# AMP.net
KiCad netlist of a schematic drawn in Altium Designer
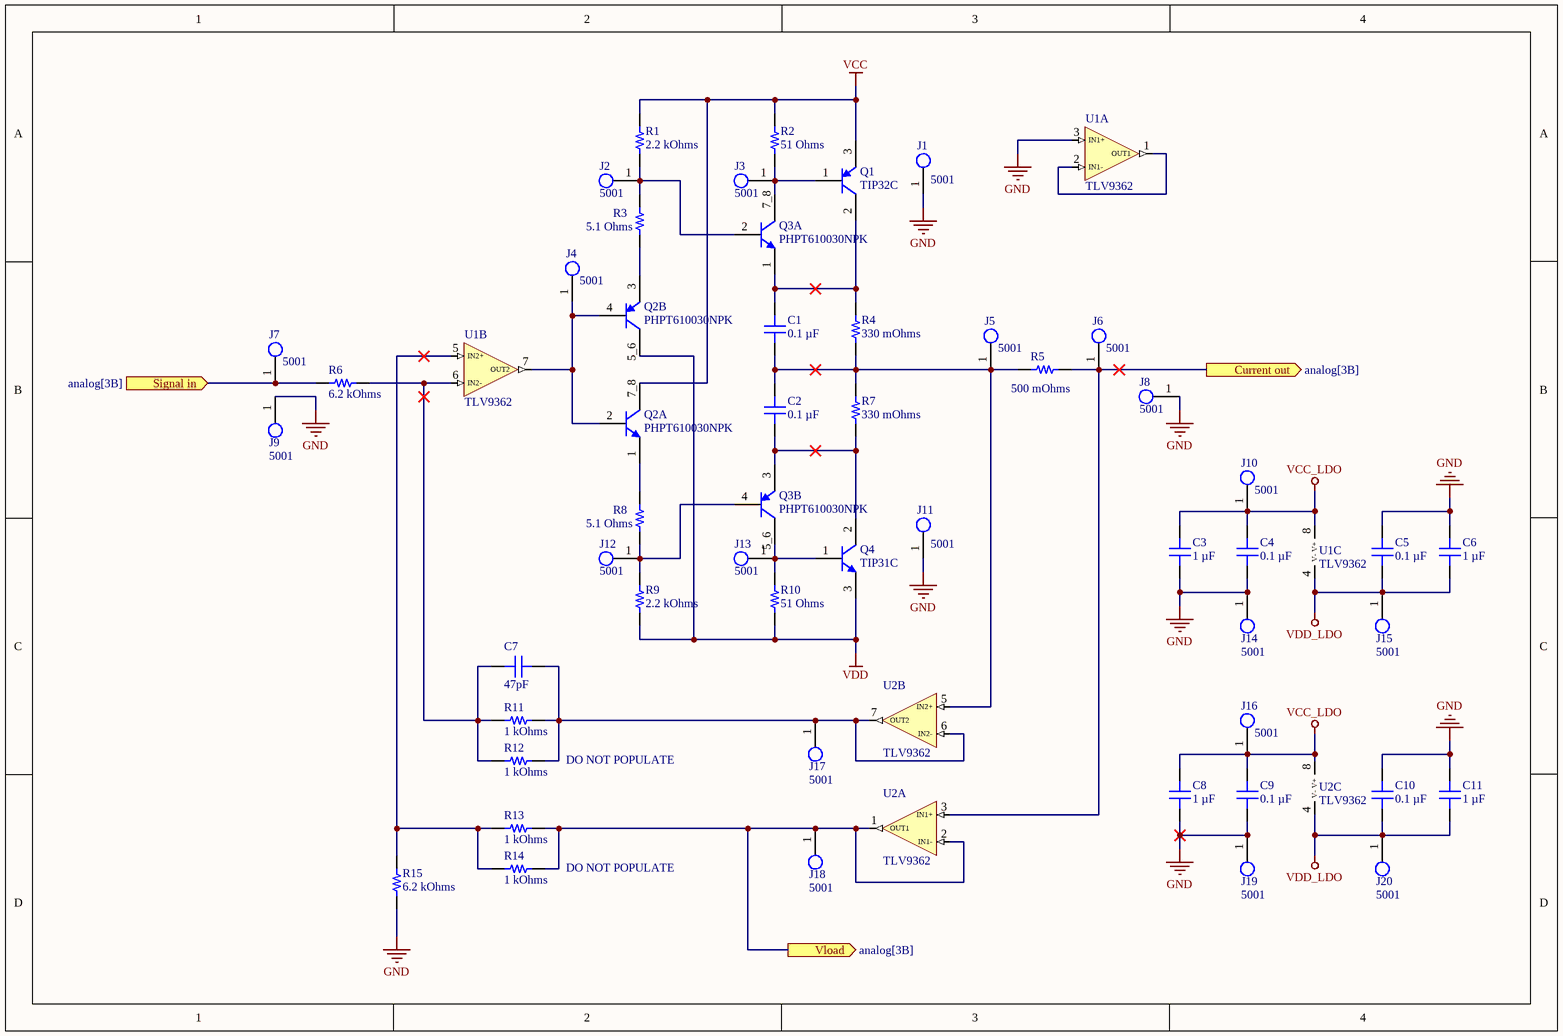
[diagram p0: AMP.SchDoc]

(export (version "E")
  (design (tool "Eeschema 10.0.6"))
  (components
    (comp (ref "C1")
      (value "0.1 µF")
      (footprint "CAP 1206_3216 - 0.8MM")
      (description "CAP CER 0.1UF 50V X7R 1206")
      (fields
        (field (name "PART NUMBER") "885012208087")
        (field (name "CAPACITANCE") "0.1 µF")
        (field (name "MANUFACTURER") "Würth Elektronik")
      )
      (libsource (lib "Celestial Altium Library - altium_library") (part "Capacitor"))
    )
    (comp (ref "C2")
      (value "0.1 µF")
      (footprint "CAP 1206_3216 - 0.8MM")
      (description "CAP CER 0.1UF 50V X7R 1206")
      (fields
        (field (name "PART NUMBER") "885012208087")
        (field (name "CAPACITANCE") "0.1 µF")
        (field (name "MANUFACTURER") "Würth Elektronik")
      )
      (libsource (lib "Celestial Altium Library - altium_library") (part "Capacitor"))
    )
    (comp (ref "C3")
      (value "1 µF")
      (footprint "CAP 1206_3216 - 0.8MM")
      (description "CAP CER 1UF 50V X7R 1206")
      (fields
        (field (name "PART NUMBER") "885012208093")
        (field (name "CAPACITANCE") "1 µF")
        (field (name "MANUFACTURER") "Würth Elektronik")
      )
      (libsource (lib "Celestial Altium Library - altium_library") (part "Capacitor"))
    )
    (comp (ref "C4")
      (value "0.1 µF")
      (footprint "CAP 1206_3216 - 0.8MM")
      (description "CAP CER 0.1UF 50V X7R 1206")
      (fields
        (field (name "PART NUMBER") "885012208087")
        (field (name "CAPACITANCE") "0.1 µF")
        (field (name "MANUFACTURER") "Würth Elektronik")
      )
      (libsource (lib "Celestial Altium Library - altium_library") (part "Capacitor"))
    )
    (comp (ref "C5")
      (value "0.1 µF")
      (footprint "CAP 1206_3216 - 0.8MM")
      (description "CAP CER 0.1UF 50V X7R 1206")
      (fields
        (field (name "PART NUMBER") "885012208087")
        (field (name "CAPACITANCE") "0.1 µF")
        (field (name "MANUFACTURER") "Würth Elektronik")
      )
      (libsource (lib "Celestial Altium Library - altium_library") (part "Capacitor"))
    )
    (comp (ref "C6")
      (value "1 µF")
      (footprint "CAP 1206_3216 - 0.8MM")
      (description "CAP CER 1UF 50V X7R 1206")
      (fields
        (field (name "PART NUMBER") "885012208093")
        (field (name "CAPACITANCE") "1 µF")
        (field (name "MANUFACTURER") "Würth Elektronik")
      )
      (libsource (lib "Celestial Altium Library - altium_library") (part "Capacitor"))
    )
    (comp (ref "C7")
      (value "47pF")
      (footprint "CAP 1206_3216 - 1.8MM")
      (description "CAP CER 47PF 1KV C0G/NP0 1206")
      (fields
        (field (name "PART NUMBER") "1206AA470KAT1A")
        (field (name "CAPACITANCE") "47pF")
        (field (name "MANUFACTURER") "AVX Corporation")
      )
      (libsource (lib "Celestial Altium Library - altium_library") (part "Capacitor"))
    )
    (comp (ref "C8")
      (value "1 µF")
      (footprint "CAP 1206_3216 - 0.8MM")
      (description "CAP CER 1UF 50V X7R 1206")
      (fields
        (field (name "PART NUMBER") "885012208093")
        (field (name "CAPACITANCE") "1 µF")
        (field (name "MANUFACTURER") "Würth Elektronik")
      )
      (libsource (lib "Celestial Altium Library - altium_library") (part "Capacitor"))
    )
    (comp (ref "C9")
      (value "0.1 µF")
      (footprint "CAP 1206_3216 - 0.8MM")
      (description "CAP CER 0.1UF 50V X7R 1206")
      (fields
        (field (name "PART NUMBER") "885012208087")
        (field (name "CAPACITANCE") "0.1 µF")
        (field (name "MANUFACTURER") "Würth Elektronik")
      )
      (libsource (lib "Celestial Altium Library - altium_library") (part "Capacitor"))
    )
    (comp (ref "C10")
      (value "0.1 µF")
      (footprint "CAP 1206_3216 - 0.8MM")
      (description "CAP CER 0.1UF 50V X7R 1206")
      (fields
        (field (name "PART NUMBER") "885012208087")
        (field (name "CAPACITANCE") "0.1 µF")
        (field (name "MANUFACTURER") "Würth Elektronik")
      )
      (libsource (lib "Celestial Altium Library - altium_library") (part "Capacitor"))
    )
    (comp (ref "C11")
      (value "1 µF")
      (footprint "CAP 1206_3216 - 0.8MM")
      (description "CAP CER 1UF 50V X7R 1206")
      (fields
        (field (name "PART NUMBER") "885012208093")
        (field (name "CAPACITANCE") "1 µF")
        (field (name "MANUFACTURER") "Würth Elektronik")
      )
      (libsource (lib "Celestial Altium Library - altium_library") (part "Capacitor"))
    )
    (comp (ref "J1")
      (value "5001")
      (footprint "FP-5001-MFG")
      (description "PC TEST POINT MINIATURE BLACK")
      (libsource (lib "za_koncar") (part "CMP-2000-05181-2"))
    )
    (comp (ref "J2")
      (value "5001")
      (footprint "FP-5001-MFG")
      (description "PC TEST POINT MINIATURE BLACK")
      (libsource (lib "za_koncar") (part "CMP-2000-05181-2"))
    )
    (comp (ref "J3")
      (value "5001")
      (footprint "FP-5001-MFG")
      (description "PC TEST POINT MINIATURE BLACK")
      (libsource (lib "za_koncar") (part "CMP-2000-05181-2"))
    )
    (comp (ref "J4")
      (value "5001")
      (footprint "FP-5001-MFG")
      (description "PC TEST POINT MINIATURE BLACK")
      (libsource (lib "za_koncar") (part "CMP-2000-05181-2"))
    )
    (comp (ref "J5")
      (value "5001")
      (footprint "FP-5001-MFG")
      (description "PC TEST POINT MINIATURE BLACK")
      (libsource (lib "za_koncar") (part "CMP-2000-05181-2"))
    )
    (comp (ref "J6")
      (value "5001")
      (footprint "FP-5001-MFG")
      (description "PC TEST POINT MINIATURE BLACK")
      (libsource (lib "za_koncar") (part "CMP-2000-05181-2"))
    )
    (comp (ref "J7")
      (value "5001")
      (footprint "FP-5001-MFG")
      (description "PC TEST POINT MINIATURE BLACK")
      (libsource (lib "za_koncar") (part "CMP-2000-05181-2"))
    )
    (comp (ref "J8")
      (value "5001")
      (footprint "FP-5001-MFG")
      (description "PC TEST POINT MINIATURE BLACK")
      (libsource (lib "za_koncar") (part "CMP-2000-05181-2"))
    )
    (comp (ref "J9")
      (value "5001")
      (footprint "FP-5001-MFG")
      (description "PC TEST POINT MINIATURE BLACK")
      (libsource (lib "za_koncar") (part "CMP-2000-05181-2"))
    )
    (comp (ref "J10")
      (value "5001")
      (footprint "FP-5001-MFG")
      (description "PC TEST POINT MINIATURE BLACK")
      (libsource (lib "za_koncar") (part "CMP-2000-05181-2"))
    )
    (comp (ref "J11")
      (value "5001")
      (footprint "FP-5001-MFG")
      (description "PC TEST POINT MINIATURE BLACK")
      (libsource (lib "za_koncar") (part "CMP-2000-05181-2"))
    )
    (comp (ref "J12")
      (value "5001")
      (footprint "FP-5001-MFG")
      (description "PC TEST POINT MINIATURE BLACK")
      (libsource (lib "za_koncar") (part "CMP-2000-05181-2"))
    )
    (comp (ref "J13")
      (value "5001")
      (footprint "FP-5001-MFG")
      (description "PC TEST POINT MINIATURE BLACK")
      (libsource (lib "za_koncar") (part "CMP-2000-05181-2"))
    )
    (comp (ref "J14")
      (value "5001")
      (footprint "FP-5001-MFG")
      (description "PC TEST POINT MINIATURE BLACK")
      (libsource (lib "za_koncar") (part "CMP-2000-05181-2"))
    )
    (comp (ref "J15")
      (value "5001")
      (footprint "FP-5001-MFG")
      (description "PC TEST POINT MINIATURE BLACK")
      (libsource (lib "za_koncar") (part "CMP-2000-05181-2"))
    )
    (comp (ref "J16")
      (value "5001")
      (footprint "FP-5001-MFG")
      (description "PC TEST POINT MINIATURE BLACK")
      (libsource (lib "za_koncar") (part "CMP-2000-05181-2"))
    )
    (comp (ref "J17")
      (value "5001")
      (footprint "FP-5001-MFG")
      (description "PC TEST POINT MINIATURE BLACK")
      (libsource (lib "za_koncar") (part "CMP-2000-05181-2"))
    )
    (comp (ref "J18")
      (value "5001")
      (footprint "FP-5001-MFG")
      (description "PC TEST POINT MINIATURE BLACK")
      (libsource (lib "za_koncar") (part "CMP-2000-05181-2"))
    )
    (comp (ref "J19")
      (value "5001")
      (footprint "FP-5001-MFG")
      (description "PC TEST POINT MINIATURE BLACK")
      (libsource (lib "za_koncar") (part "CMP-2000-05181-2"))
    )
    (comp (ref "J20")
      (value "5001")
      (footprint "FP-5001-MFG")
      (description "PC TEST POINT MINIATURE BLACK")
      (libsource (lib "za_koncar") (part "CMP-2000-05181-2"))
    )
    (comp (ref "Q1")
      (value "TIP32C")
      (footprint "ONSC-TO-220-3-221A-09")
      (description "Complementary Silicon Plastic Power Transistor, 3-Pin TO-220, Tube")
      (fields (field (name "MANUFACTURER") "On Semiconductor"))
      (libsource (lib "ON Semi General Purpose Transistors") (part "TIP32C"))
    )
    (comp (ref "Q2")
      (value "PHPT610030NPK")
      (footprint "TRANS_BUK9K18-40E,115")
      (libsource (lib "za_koncar") (part "PHPT610030NPK"))
    )
    (comp (ref "Q3")
      (value "PHPT610030NPK")
      (footprint "TRANS_BUK9K18-40E,115")
      (libsource (lib "za_koncar") (part "PHPT610030NPK"))
    )
    (comp (ref "Q4")
      (value "TIP31C")
      (footprint "ONSC-TO-220-3-221A-09")
      (description "Complementary Silicon Plastic Power Transistor, 3-Pin TO-220, Tube")
      (fields (field (name "MANUFACTURER") "On Semiconductor"))
      (libsource (lib "ON Semi General Purpose Transistors") (part "TIP31C"))
    )
    (comp (ref "R1")
      (value "2.2 kOhms")
      (footprint "RES 1206_3216")
      (description "RES SMD 2.2K OHM 5% 1/4W 1206")
      (fields
        (field (name "PART NUMBER") "ERJ-8GEYJ222V")
        (field (name "MANUFACTURER") "Panasonic Electronic Components")
      )
      (libsource (lib "Celestial Altium Library - altium_library") (part "Resistor"))
    )
    (comp (ref "R2")
      (value "51 Ohms")
      (footprint "RES 1206_3216")
      (description "RES SMD 51 OHM 5% 1/4W 1206")
      (fields
        (field (name "PART NUMBER") "ERJ-8GEYJ510V")
        (field (name "MANUFACTURER") "Panasonic Electronic Components")
      )
      (libsource (lib "Celestial Altium Library - altium_library") (part "Resistor"))
    )
    (comp (ref "R3")
      (value "5.1 Ohms")
      (footprint "RES 1206_3216")
      (description "RES SMD 5.1 OHM 5% 1/4W 1206")
      (fields
        (field (name "PART NUMBER") "ERJ-8GEYJ5R1V")
        (field (name "MANUFACTURER") "Panasonic Electronic Components")
      )
      (libsource (lib "Celestial Altium Library - altium_library") (part "Resistor"))
    )
    (comp (ref "R4")
      (value "330 mOhms")
      (footprint "STACKPOLE CSR2512")
      (description "RES 0.33 OHM 1% 2W 2512")
      (fields
        (field (name "PART NUMBER") "CSRN2512FKR330")
        (field (name "MANUFACTURER") "Stackpole Electronics Inc")
      )
      (libsource (lib "Celestial Altium Library - altium_library") (part "Resistor"))
    )
    (comp (ref "R5")
      (value "500 mOhms")
      (footprint "STACKPOLE CSR2512")
      (description "RES 0.5 OHM 1% 2W 2512")
      (fields
        (field (name "PART NUMBER") "CSRN2512FKR500")
        (field (name "MANUFACTURER") "Stackpole Electronics Inc")
      )
      (libsource (lib "Celestial Altium Library - altium_library") (part "Resistor"))
    )
    (comp (ref "R6")
      (value "6.2 kOhms")
      (footprint "RES 1206_3216")
      (description "RES SMD 6.2K OHM 0.1% 1/4W 1206")
      (fields
        (field (name "PART NUMBER") "ERA-8AEB622V")
        (field (name "MANUFACTURER") "Panasonic Electronic Components")
      )
      (libsource (lib "Celestial Altium Library - altium_library") (part "Resistor"))
    )
    (comp (ref "R7")
      (value "330 mOhms")
      (footprint "STACKPOLE CSR2512")
      (description "RES 0.33 OHM 1% 2W 2512")
      (fields
        (field (name "PART NUMBER") "CSRN2512FKR330")
        (field (name "MANUFACTURER") "Stackpole Electronics Inc")
      )
      (libsource (lib "Celestial Altium Library - altium_library") (part "Resistor"))
    )
    (comp (ref "R8")
      (value "5.1 Ohms")
      (footprint "RES 1206_3216")
      (description "RES SMD 5.1 OHM 5% 1/4W 1206")
      (fields
        (field (name "PART NUMBER") "ERJ-8GEYJ5R1V")
        (field (name "MANUFACTURER") "Panasonic Electronic Components")
      )
      (libsource (lib "Celestial Altium Library - altium_library") (part "Resistor"))
    )
    (comp (ref "R9")
      (value "2.2 kOhms")
      (footprint "RES 1206_3216")
      (description "RES SMD 2.2K OHM 5% 1/4W 1206")
      (fields
        (field (name "PART NUMBER") "ERJ-8GEYJ222V")
        (field (name "MANUFACTURER") "Panasonic Electronic Components")
      )
      (libsource (lib "Celestial Altium Library - altium_library") (part "Resistor"))
    )
    (comp (ref "R10")
      (value "51 Ohms")
      (footprint "RES 1206_3216")
      (description "RES SMD 51 OHM 5% 1/4W 1206")
      (fields
        (field (name "PART NUMBER") "ERJ-8GEYJ510V")
        (field (name "MANUFACTURER") "Panasonic Electronic Components")
      )
      (libsource (lib "Celestial Altium Library - altium_library") (part "Resistor"))
    )
    (comp (ref "R11")
      (value "1 kOhms")
      (footprint "RES 1206_3216")
      (description "RES SMD 1K OHM 0.1% 1/4W 1206")
      (fields
        (field (name "PART NUMBER") "ERA-8AEB102V")
        (field (name "MANUFACTURER") "Panasonic Electronic Components")
      )
      (libsource (lib "Celestial Altium Library - altium_library") (part "Resistor"))
    )
    (comp (ref "R12")
      (value "1 kOhms")
      (footprint "RES 1206_3216")
      (description "RES SMD 1K OHM 0.1% 1/4W 1206")
      (fields
        (field (name "PART NUMBER") "ERA-8AEB102V")
        (field (name "MANUFACTURER") "Panasonic Electronic Components")
      )
      (libsource (lib "Celestial Altium Library - altium_library") (part "Resistor"))
    )
    (comp (ref "R13")
      (value "1 kOhms")
      (footprint "RES 1206_3216")
      (description "RES SMD 1K OHM 0.1% 1/4W 1206")
      (fields
        (field (name "PART NUMBER") "ERA-8AEB102V")
        (field (name "MANUFACTURER") "Panasonic Electronic Components")
      )
      (libsource (lib "Celestial Altium Library - altium_library") (part "Resistor"))
    )
    (comp (ref "R14")
      (value "1 kOhms")
      (footprint "RES 1206_3216")
      (description "RES SMD 1K OHM 0.1% 1/4W 1206")
      (fields
        (field (name "PART NUMBER") "ERA-8AEB102V")
        (field (name "MANUFACTURER") "Panasonic Electronic Components")
      )
      (libsource (lib "Celestial Altium Library - altium_library") (part "Resistor"))
    )
    (comp (ref "R15")
      (value "6.2 kOhms")
      (footprint "RES 1206_3216")
      (description "RES SMD 6.2K OHM 0.1% 1/4W 1206")
      (fields
        (field (name "PART NUMBER") "ERA-8AEB622V")
        (field (name "MANUFACTURER") "Panasonic Electronic Components")
      )
      (libsource (lib "Celestial Altium Library - altium_library") (part "Resistor"))
    )
    (comp (ref "U1")
      (value "TLV9362")
      (footprint "za_koncar:SOIC8-127P600X175-8N")
      (description "TLV936x 10-MHz, 40-V, RRO, Operational Amplifie")
      (libsource (lib "za_koncar") (part "TLV9362"))
    )
    (comp (ref "U2")
      (value "TLV9362")
      (footprint "za_koncar:SOIC8-127P600X175-8N")
      (description "TLV936x 10-MHz, 40-V, RRO, Operational Amplifie")
      (libsource (lib "za_koncar") (part "TLV9362"))
    )
  )
  (nets
    (net (code "1") (name "/Current out") (class "Default")
      (node (ref "J6") (pin "1") (pinfunction "1_1") (pintype "passive"))
      (node (ref "R5") (pin "1") (pinfunction "1_1") (pintype "passive"))
      (node (ref "U2") (pin "3") (pinfunction "IN1+_3") (pintype "input"))
    )
    (net (code "2") (name "/Signal in") (class "Default")
      (node (ref "J7") (pin "1") (pinfunction "1_1") (pintype "passive"))
      (node (ref "R6") (pin "2") (pinfunction "2_2") (pintype "passive"))
    )
    (net (code "3") (name "/Vload") (class "Default")
      (node (ref "J18") (pin "1") (pinfunction "1_1") (pintype "passive"))
      (node (ref "R13") (pin "2") (pinfunction "2_2") (pintype "passive"))
      (node (ref "R14") (pin "2") (pinfunction "2_2") (pintype "passive"))
      (node (ref "U2") (pin "1") (pinfunction "OUT1_1") (pintype "output"))
      (node (ref "U2") (pin "2") (pinfunction "IN1-_2") (pintype "input"))
    )
    (net (code "4") (name "GND") (class "Default")
      (node (ref "C10") (pin "2") (pinfunction "2_2") (pintype "passive"))
      (node (ref "C11") (pin "2") (pinfunction "2_2") (pintype "passive"))
      (node (ref "C3") (pin "1") (pinfunction "1_1") (pintype "passive"))
      (node (ref "C4") (pin "1") (pinfunction "1_1") (pintype "passive"))
      (node (ref "C5") (pin "2") (pinfunction "2_2") (pintype "passive"))
      (node (ref "C6") (pin "2") (pinfunction "2_2") (pintype "passive"))
      (node (ref "C8") (pin "1") (pinfunction "1_1") (pintype "passive"))
      (node (ref "C9") (pin "1") (pinfunction "1_1") (pintype "passive"))
      (node (ref "J1") (pin "1") (pinfunction "1_1") (pintype "passive"))
      (node (ref "J11") (pin "1") (pinfunction "1_1") (pintype "passive"))
      (node (ref "J14") (pin "1") (pinfunction "1_1") (pintype "passive"))
      (node (ref "J19") (pin "1") (pinfunction "1_1") (pintype "passive"))
      (node (ref "J8") (pin "1") (pinfunction "1_1") (pintype "passive"))
      (node (ref "J9") (pin "1") (pinfunction "1_1") (pintype "passive"))
      (node (ref "R15") (pin "1") (pinfunction "1_1") (pintype "passive"))
      (node (ref "U1") (pin "3") (pinfunction "IN1+_3") (pintype "input"))
    )
    (net (code "5") (name "Net-(Q1-B)") (class "Default")
      (node (ref "J3") (pin "1") (pinfunction "1_1") (pintype "passive"))
      (node (ref "Q1") (pin "1") (pinfunction "B_1") (pintype "passive"))
      (node (ref "Q3") (pin "7_8") (pinfunction "C1_7_8") (pintype "passive"))
      (node (ref "R2") (pin "1") (pinfunction "1_1") (pintype "passive"))
    )
    (net (code "6") (name "Net-(Q1-C)") (class "Default")
      (node (ref "C1") (pin "2") (pinfunction "2_2") (pintype "passive"))
      (node (ref "Q1") (pin "2") (pinfunction "C_2") (pintype "passive"))
      (node (ref "Q3") (pin "1") (pinfunction "E1_1") (pintype "passive"))
      (node (ref "R4") (pin "2") (pinfunction "2_2") (pintype "passive"))
    )
    (net (code "7") (name "Net-(Q2A-B1)") (class "Default")
      (node (ref "J4") (pin "1") (pinfunction "1_1") (pintype "passive"))
      (node (ref "Q2") (pin "2") (pinfunction "B1_2") (pintype "passive"))
      (node (ref "Q2") (pin "4") (pinfunction "B2_4") (pintype "passive"))
      (node (ref "U1") (pin "7") (pinfunction "OUT2_7") (pintype "output"))
    )
    (net (code "8") (name "Net-(Q2A-E1)") (class "Default")
      (node (ref "Q2") (pin "1") (pinfunction "E1_1") (pintype "passive"))
      (node (ref "R8") (pin "2") (pinfunction "2_2") (pintype "passive"))
    )
    (net (code "9") (name "Net-(Q2B-E2)") (class "Default")
      (node (ref "Q2") (pin "3") (pinfunction "E2_3") (pintype "passive"))
      (node (ref "R3") (pin "1") (pinfunction "1_1") (pintype "passive"))
    )
    (net (code "10") (name "Net-(Q3A-B1)") (class "Default")
      (node (ref "J2") (pin "1") (pinfunction "1_1") (pintype "passive"))
      (node (ref "Q3") (pin "2") (pinfunction "B1_2") (pintype "passive"))
      (node (ref "R1") (pin "1") (pinfunction "1_1") (pintype "passive"))
      (node (ref "R3") (pin "2") (pinfunction "2_2") (pintype "passive"))
    )
    (net (code "11") (name "Net-(Q3B-B2)") (class "Default")
      (node (ref "J12") (pin "1") (pinfunction "1_1") (pintype "passive"))
      (node (ref "Q3") (pin "4") (pinfunction "B2_4") (pintype "passive"))
      (node (ref "R8") (pin "1") (pinfunction "1_1") (pintype "passive"))
      (node (ref "R9") (pin "2") (pinfunction "2_2") (pintype "passive"))
    )
    (net (code "12") (name "Net-(Q3B-C2)") (class "Default")
      (node (ref "J13") (pin "1") (pinfunction "1_1") (pintype "passive"))
      (node (ref "Q3") (pin "5_6") (pinfunction "C2_5_6") (pintype "passive"))
      (node (ref "Q4") (pin "1") (pinfunction "B_1") (pintype "passive"))
      (node (ref "R10") (pin "2") (pinfunction "2_2") (pintype "passive"))
    )
    (net (code "13") (name "Net-(Q3B-E2)") (class "Default")
      (node (ref "C2") (pin "1") (pinfunction "1_1") (pintype "passive"))
      (node (ref "Q3") (pin "3") (pinfunction "E2_3") (pintype "passive"))
      (node (ref "Q4") (pin "2") (pinfunction "C_2") (pintype "passive"))
      (node (ref "R7") (pin "1") (pinfunction "1_1") (pintype "passive"))
    )
    (net (code "14") (name "Net-(U1A-IN1-)") (class "Default")
      (node (ref "U1") (pin "1") (pinfunction "OUT1_1") (pintype "output"))
      (node (ref "U1") (pin "2") (pinfunction "IN1-_2") (pintype "input"))
    )
    (net (code "15") (name "Net-(U1B-IN2+)") (class "Default")
      (node (ref "R13") (pin "1") (pinfunction "1_1") (pintype "passive"))
      (node (ref "R14") (pin "1") (pinfunction "1_1") (pintype "passive"))
      (node (ref "R15") (pin "2") (pinfunction "2_2") (pintype "passive"))
      (node (ref "U1") (pin "5") (pinfunction "IN2+_5") (pintype "input"))
    )
    (net (code "16") (name "Net-(U1B-IN2-)") (class "Default")
      (node (ref "C7") (pin "1") (pinfunction "1_1") (pintype "passive"))
      (node (ref "R11") (pin "1") (pinfunction "1_1") (pintype "passive"))
      (node (ref "R12") (pin "1") (pinfunction "1_1") (pintype "passive"))
      (node (ref "R6") (pin "1") (pinfunction "1_1") (pintype "passive"))
      (node (ref "U1") (pin "6") (pinfunction "IN2-_6") (pintype "input"))
    )
    (net (code "17") (name "Net-(U2B-IN2+)") (class "Default")
      (node (ref "C1") (pin "1") (pinfunction "1_1") (pintype "passive"))
      (node (ref "C2") (pin "2") (pinfunction "2_2") (pintype "passive"))
      (node (ref "J5") (pin "1") (pinfunction "1_1") (pintype "passive"))
      (node (ref "R4") (pin "1") (pinfunction "1_1") (pintype "passive"))
      (node (ref "R5") (pin "2") (pinfunction "2_2") (pintype "passive"))
      (node (ref "R7") (pin "2") (pinfunction "2_2") (pintype "passive"))
      (node (ref "U2") (pin "5") (pinfunction "IN2+_5") (pintype "input"))
    )
    (net (code "18") (name "Net-(U2B-IN2-)") (class "Default")
      (node (ref "C7") (pin "2") (pinfunction "2_2") (pintype "passive"))
      (node (ref "J17") (pin "1") (pinfunction "1_1") (pintype "passive"))
      (node (ref "R11") (pin "2") (pinfunction "2_2") (pintype "passive"))
      (node (ref "R12") (pin "2") (pinfunction "2_2") (pintype "passive"))
      (node (ref "U2") (pin "6") (pinfunction "IN2-_6") (pintype "input"))
      (node (ref "U2") (pin "7") (pinfunction "OUT2_7") (pintype "output"))
    )
    (net (code "19") (name "VCC") (class "Default")
      (node (ref "Q1") (pin "3") (pinfunction "E_3") (pintype "passive"))
      (node (ref "Q2") (pin "7_8") (pinfunction "C1_7_8") (pintype "passive"))
      (node (ref "R1") (pin "2") (pinfunction "2_2") (pintype "passive"))
      (node (ref "R2") (pin "2") (pinfunction "2_2") (pintype "passive"))
    )
    (net (code "20") (name "VCC_LDO") (class "Default")
      (node (ref "C3") (pin "2") (pinfunction "2_2") (pintype "passive"))
      (node (ref "C4") (pin "2") (pinfunction "2_2") (pintype "passive"))
      (node (ref "C8") (pin "2") (pinfunction "2_2") (pintype "passive"))
      (node (ref "C9") (pin "2") (pinfunction "2_2") (pintype "passive"))
      (node (ref "J10") (pin "1") (pinfunction "1_1") (pintype "passive"))
      (node (ref "J16") (pin "1") (pinfunction "1_1") (pintype "passive"))
      (node (ref "U1") (pin "8") (pinfunction "V+_8") (pintype "power_in"))
      (node (ref "U2") (pin "8") (pinfunction "V+_8") (pintype "power_in"))
    )
    (net (code "21") (name "VDD") (class "Default")
      (node (ref "Q2") (pin "5_6") (pinfunction "C2_5_6") (pintype "passive"))
      (node (ref "Q4") (pin "3") (pinfunction "E_3") (pintype "passive"))
      (node (ref "R10") (pin "1") (pinfunction "1_1") (pintype "passive"))
      (node (ref "R9") (pin "1") (pinfunction "1_1") (pintype "passive"))
    )
    (net (code "22") (name "VDD_LDO") (class "Default")
      (node (ref "C10") (pin "1") (pinfunction "1_1") (pintype "passive"))
      (node (ref "C11") (pin "1") (pinfunction "1_1") (pintype "passive"))
      (node (ref "C5") (pin "1") (pinfunction "1_1") (pintype "passive"))
      (node (ref "C6") (pin "1") (pinfunction "1_1") (pintype "passive"))
      (node (ref "J15") (pin "1") (pinfunction "1_1") (pintype "passive"))
      (node (ref "J20") (pin "1") (pinfunction "1_1") (pintype "passive"))
      (node (ref "U1") (pin "4") (pinfunction "V-_4") (pintype "power_in"))
      (node (ref "U2") (pin "4") (pinfunction "V-_4") (pintype "power_in"))
    )
  )
)
